# sch_USB3_0.net
KiCad netlist of a schematic drawn in Altium Designer
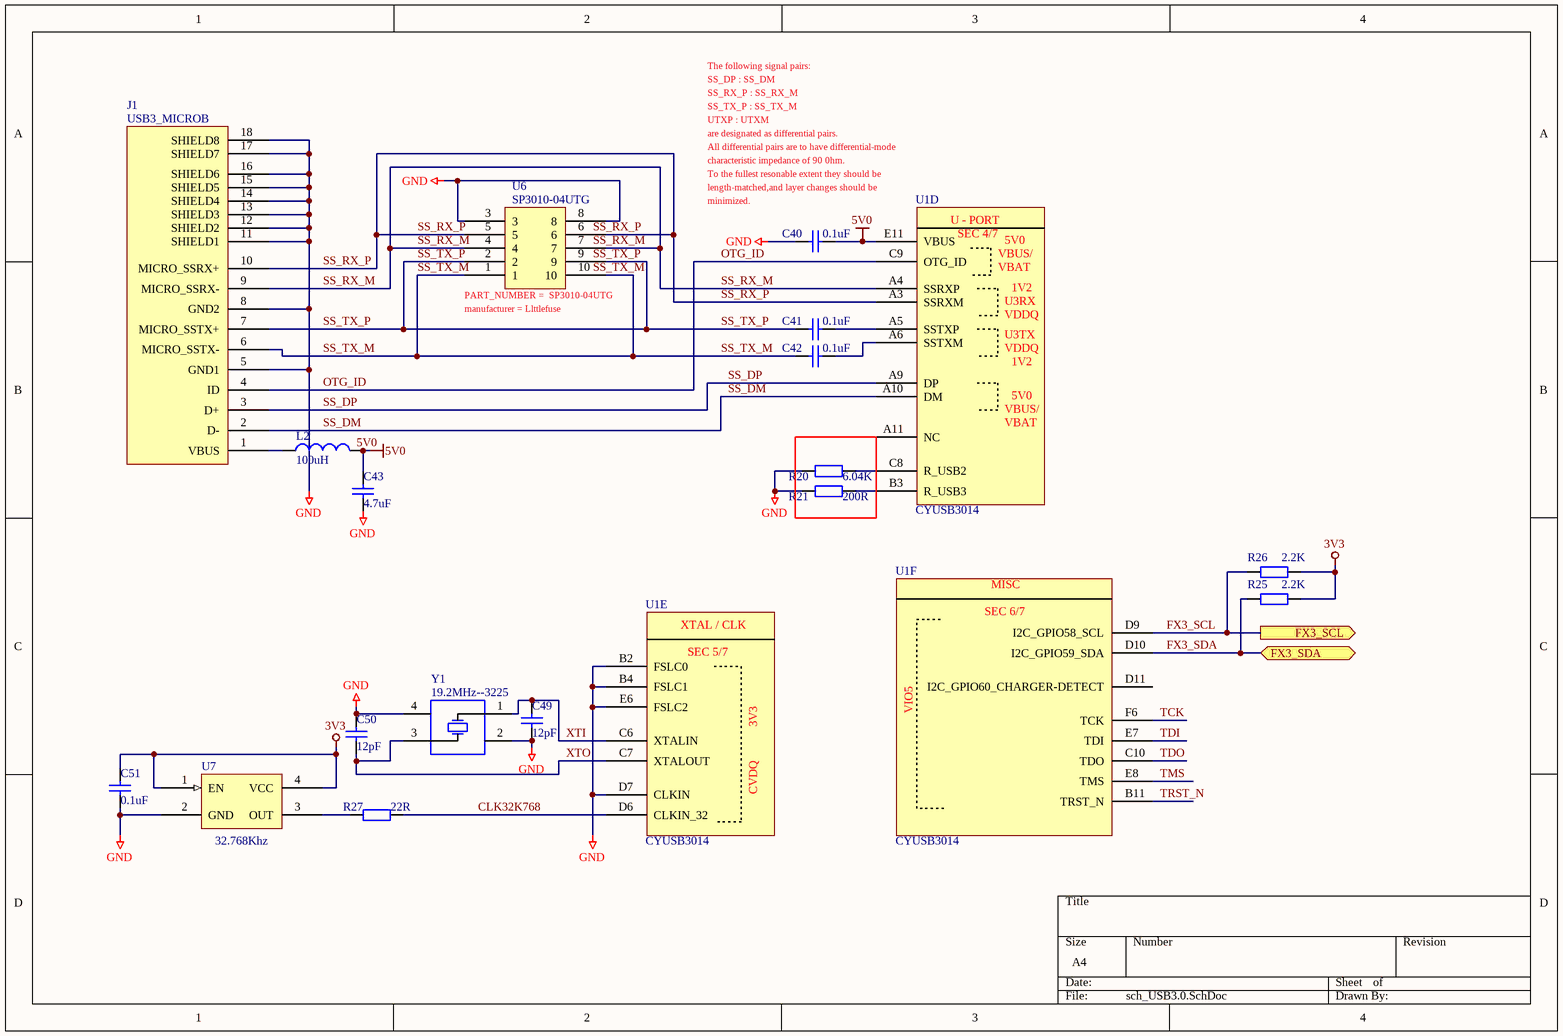
[diagram p0: sch_USB3.0.SchDoc]

(export (version "E")
  (design (tool "Eeschema 10.0.6"))
  (components
    (comp (ref "C40")
      (value "0.1uF")
      (footprint "0402C")
      (description "Capacitor")
      (fields (field (name "PUBLISHER") "Altium Limited"))
      (libsource (lib "Miscellaneous Devices") (part "Cap"))
    )
    (comp (ref "C41")
      (value "0.1uF")
      (footprint "0402C")
      (description "Capacitor")
      (fields (field (name "PUBLISHER") "Altium Limited"))
      (libsource (lib "Miscellaneous Devices") (part "Cap"))
    )
    (comp (ref "C42")
      (value "0.1uF")
      (footprint "0402C")
      (description "Capacitor")
      (fields (field (name "PUBLISHER") "Altium Limited"))
      (libsource (lib "Miscellaneous Devices") (part "Cap"))
    )
    (comp (ref "C43")
      (value "4.7uF")
      (description "Capacitor")
      (fields (field (name "PUBLISHER") "Altium Limited"))
      (libsource (lib "Miscellaneous Devices") (part "Cap"))
    )
    (comp (ref "C49")
      (value "12pF")
      (footprint "0402C")
      (description "Capacitor")
      (fields (field (name "PUBLISHER") "Altium Limited"))
      (libsource (lib "Miscellaneous Devices") (part "Cap"))
    )
    (comp (ref "C50")
      (value "12pF")
      (footprint "0402C")
      (description "Capacitor")
      (fields (field (name "PUBLISHER") "Altium Limited"))
      (libsource (lib "Miscellaneous Devices") (part "Cap"))
    )
    (comp (ref "C51")
      (value "0.1uF")
      (footprint "0402C")
      (description "Capacitor")
      (fields (field (name "PUBLISHER") "Altium Limited"))
      (libsource (lib "Miscellaneous Devices") (part "Cap"))
    )
    (comp (ref "J1")
      (value "USB3_MICROB")
      (footprint "USB3_BA_P65L130W51H28")
      (libsource (lib "SZG") (part "USB3_MICROB"))
    )
    (comp (ref "L2")
      (value "100uH")
      (description "Inductor")
      (libsource (lib "SWUST_ROBOT") (part "Inductor"))
    )
    (comp (ref "R20")
      (value "6.04K")
      (footprint "0402R")
      (description "Resistor")
      (fields (field (name "PUBLISHER") "Altium Limited"))
      (libsource (lib "SZG") (part "Resistor"))
    )
    (comp (ref "R21")
      (value "200R")
      (footprint "0402R")
      (description "Resistor")
      (fields (field (name "PUBLISHER") "Altium Limited"))
      (libsource (lib "SZG") (part "Resistor"))
    )
    (comp (ref "R25")
      (value "2.2K")
      (footprint "0402R")
      (description "Resistor")
      (fields (field (name "PUBLISHER") "Altium Limited"))
      (libsource (lib "SZG") (part "Resistor"))
    )
    (comp (ref "R26")
      (value "2.2K")
      (footprint "0402R")
      (description "Resistor")
      (fields (field (name "PUBLISHER") "Altium Limited"))
      (libsource (lib "SZG") (part "Resistor"))
    )
    (comp (ref "R27")
      (value "22R")
      (footprint "0402R")
      (description "Resistor")
      (fields (field (name "PUBLISHER") "Altium Limited"))
      (libsource (lib "SZG") (part "Resistor"))
    )
    (comp (ref "U1")
      (value "CYUSB3014")
      (footprint "FBGA121_P80L100W100H11")
      (libsource (lib "TXW") (part "CYUSB3014"))
    )
    (comp (ref "U6")
      (value "SP3010-04UTG")
      (footprint "UDFN10_SON_P50L25W10H55")
      (libsource (lib "SZG") (part "SP3010-04UTG"))
    )
    (comp (ref "U7")
      (value "XTAL-3225")
      (footprint "XTAL_3225")
      (libsource (lib "常用晶振器件图SCH") (part "XTAL."))
    )
    (comp (ref "Y1")
      (value "19.2MHz--3225")
      (footprint "XTAL_3225")
      (description "Crystal Oscillator")
      (libsource (lib "常用晶振器件图SCH") (part "XTAL"))
    )
  )
  (nets
    (net (code "1") (name "/CLK32K768") (class "Default")
      (node (ref "R27") (pin "1") (pinfunction "1_1") (pintype "passive"))
      (node (ref "U1") (pin "D6") (pinfunction "CLKIN_32_D6") (pintype "passive"))
    )
    (net (code "2") (name "/FX3_SCL") (class "Default")
      (node (ref "R26") (pin "2") (pinfunction "2_2") (pintype "passive"))
      (node (ref "U1") (pin "D9") (pinfunction "I2C_GPIO58_SCL_D9") (pintype "passive"))
    )
    (net (code "3") (name "/FX3_SDA") (class "Default")
      (node (ref "R25") (pin "2") (pinfunction "2_2") (pintype "passive"))
      (node (ref "U1") (pin "D10") (pinfunction "I2C_GPIO59_SDA_D10") (pintype "passive"))
    )
    (net (code "4") (name "/OTG_ID") (class "Default")
      (node (ref "J1") (pin "4") (pinfunction "ID_4") (pintype "power_in"))
      (node (ref "U1") (pin "C9") (pinfunction "OTG_ID_C9") (pintype "power_in"))
    )
    (net (code "5") (name "/SS_DM") (class "Default")
      (node (ref "J1") (pin "2") (pinfunction "D-_2") (pintype "power_in"))
      (node (ref "U1") (pin "A10") (pinfunction "DM_A10") (pintype "power_in"))
    )
    (net (code "6") (name "/SS_DP") (class "Default")
      (node (ref "J1") (pin "3") (pinfunction "D+_3") (pintype "power_in"))
      (node (ref "U1") (pin "A9") (pinfunction "DP_A9") (pintype "power_in"))
    )
    (net (code "7") (name "/SS_RX_M") (class "Default")
      (node (ref "J1") (pin "9") (pinfunction "MICRO_SSRX-_9") (pintype "power_in"))
      (node (ref "U1") (pin "A4") (pinfunction "SSRXP_A4") (pintype "power_in"))
      (node (ref "U6") (pin "4") (pinfunction "4_4") (pintype "passive"))
      (node (ref "U6") (pin "7") (pinfunction "7_7") (pintype "passive"))
    )
    (net (code "8") (name "/SS_RX_P") (class "Default")
      (node (ref "J1") (pin "10") (pinfunction "MICRO_SSRX+_10") (pintype "power_in"))
      (node (ref "U1") (pin "A3") (pinfunction "SSRXM_A3") (pintype "power_in"))
      (node (ref "U6") (pin "5") (pinfunction "5_5") (pintype "passive"))
      (node (ref "U6") (pin "6") (pinfunction "6_6") (pintype "passive"))
    )
    (net (code "9") (name "/SS_TX_M") (class "Default")
      (node (ref "C42") (pin "2") (pinfunction "2_2") (pintype "passive"))
      (node (ref "J1") (pin "6") (pinfunction "MICRO_SSTX-_6") (pintype "power_in"))
      (node (ref "U6") (pin "1") (pinfunction "1_1") (pintype "passive"))
      (node (ref "U6") (pin "10") (pinfunction "10_10") (pintype "passive"))
    )
    (net (code "10") (name "/SS_TX_P") (class "Default")
      (node (ref "C41") (pin "2") (pinfunction "2_2") (pintype "passive"))
      (node (ref "J1") (pin "7") (pinfunction "MICRO_SSTX+_7") (pintype "power_in"))
      (node (ref "U6") (pin "2") (pinfunction "2_2") (pintype "passive"))
      (node (ref "U6") (pin "9") (pinfunction "9_9") (pintype "passive"))
    )
    (net (code "11") (name "/TCK") (class "Default")
      (node (ref "U1") (pin "F6") (pinfunction "TCK_F6") (pintype "passive"))
    )
    (net (code "12") (name "/TDI") (class "Default")
      (node (ref "U1") (pin "E7") (pinfunction "TDI_E7") (pintype "passive"))
    )
    (net (code "13") (name "/TDO") (class "Default")
      (node (ref "U1") (pin "C10") (pinfunction "TDO_C10") (pintype "passive"))
    )
    (net (code "14") (name "/TMS") (class "Default")
      (node (ref "U1") (pin "E8") (pinfunction "TMS_E8") (pintype "passive"))
    )
    (net (code "15") (name "/TRST_N") (class "Default")
      (node (ref "U1") (pin "B11") (pinfunction "TRST_N_B11") (pintype "passive"))
    )
    (net (code "16") (name "/XTI") (class "Default")
      (node (ref "C49") (pin "2") (pinfunction "2_2") (pintype "passive"))
      (node (ref "U1") (pin "C6") (pinfunction "XTALIN_C6") (pintype "passive"))
      (node (ref "Y1") (pin "1") (pinfunction "1_1") (pintype "passive"))
    )
    (net (code "17") (name "/XTO") (class "Default")
      (node (ref "C50") (pin "1") (pinfunction "1_1") (pintype "passive"))
      (node (ref "U1") (pin "C7") (pinfunction "XTALOUT_C7") (pintype "passive"))
      (node (ref "Y1") (pin "3") (pinfunction "3_3") (pintype "passive"))
    )
    (net (code "18") (name "3V3") (class "Default")
      (node (ref "C51") (pin "2") (pinfunction "2_2") (pintype "passive"))
      (node (ref "R25") (pin "1") (pinfunction "1_1") (pintype "passive"))
      (node (ref "R26") (pin "1") (pinfunction "1_1") (pintype "passive"))
      (node (ref "U7") (pin "1") (pinfunction "EN_1") (pintype "input"))
      (node (ref "U7") (pin "4") (pinfunction "VCC_4") (pintype "passive"))
    )
    (net (code "19") (name "5V0") (class "Default")
      (node (ref "C40") (pin "1") (pinfunction "1_1") (pintype "passive"))
      (node (ref "C43") (pin "2") (pinfunction "2_2") (pintype "passive"))
      (node (ref "L2") (pin "2") (pinfunction "2_2") (pintype "passive"))
      (node (ref "U1") (pin "E11") (pinfunction "VBUS_E11") (pintype "power_in"))
    )
    (net (code "20") (name "GND") (class "Default")
      (node (ref "C40") (pin "2") (pinfunction "2_2") (pintype "passive"))
      (node (ref "C43") (pin "1") (pinfunction "1_1") (pintype "passive"))
      (node (ref "C49") (pin "1") (pinfunction "1_1") (pintype "passive"))
      (node (ref "C50") (pin "2") (pinfunction "2_2") (pintype "passive"))
      (node (ref "C51") (pin "1") (pinfunction "1_1") (pintype "passive"))
      (node (ref "J1") (pin "11") (pinfunction "SHIELD1_11") (pintype "power_in"))
      (node (ref "J1") (pin "12") (pinfunction "SHIELD2_12") (pintype "power_in"))
      (node (ref "J1") (pin "13") (pinfunction "SHIELD3_13") (pintype "power_in"))
      (node (ref "J1") (pin "14") (pinfunction "SHIELD4_14") (pintype "power_in"))
      (node (ref "J1") (pin "15") (pinfunction "SHIELD5_15") (pintype "power_in"))
      (node (ref "J1") (pin "16") (pinfunction "SHIELD6_16") (pintype "power_in"))
      (node (ref "J1") (pin "17") (pinfunction "SHIELD7_17") (pintype "power_in"))
      (node (ref "J1") (pin "18") (pinfunction "SHIELD8_18") (pintype "power_in"))
      (node (ref "J1") (pin "5") (pinfunction "GND1_5") (pintype "power_in"))
      (node (ref "J1") (pin "8") (pinfunction "GND2_8") (pintype "power_in"))
      (node (ref "R20") (pin "2") (pinfunction "2_2") (pintype "passive"))
      (node (ref "R21") (pin "2") (pinfunction "2_2") (pintype "passive"))
      (node (ref "U1") (pin "B2") (pinfunction "FSLC0_B2") (pintype "passive"))
      (node (ref "U1") (pin "B4") (pinfunction "FSLC1_B4") (pintype "passive"))
      (node (ref "U1") (pin "D7") (pinfunction "CLKIN_D7") (pintype "passive"))
      (node (ref "U1") (pin "E6") (pinfunction "FSLC2_E6") (pintype "passive"))
      (node (ref "U6") (pin "3") (pinfunction "3_3") (pintype "passive"))
      (node (ref "U6") (pin "8") (pinfunction "8_8") (pintype "passive"))
      (node (ref "U7") (pin "2") (pinfunction "GND_2") (pintype "passive"))
      (node (ref "Y1") (pin "2") (pinfunction "2_2") (pintype "passive"))
      (node (ref "Y1") (pin "4") (pinfunction "4_4") (pintype "passive"))
    )
    (net (code "21") (name "Net-(J1-VBUS)") (class "Default")
      (node (ref "J1") (pin "1") (pinfunction "VBUS_1") (pintype "power_in"))
      (node (ref "L2") (pin "1") (pinfunction "1_1") (pintype "passive"))
    )
    (net (code "22") (name "Net-(U1D-R_USB2)") (class "Default")
      (node (ref "R20") (pin "1") (pinfunction "1_1") (pintype "passive"))
      (node (ref "U1") (pin "C8") (pinfunction "R_USB2_C8") (pintype "power_in"))
    )
    (net (code "23") (name "Net-(U1D-R_USB3)") (class "Default")
      (node (ref "R21") (pin "1") (pinfunction "1_1") (pintype "passive"))
      (node (ref "U1") (pin "B3") (pinfunction "R_USB3_B3") (pintype "power_in"))
    )
    (net (code "24") (name "Net-(U1D-SSTXM)") (class "Default")
      (node (ref "C42") (pin "1") (pinfunction "1_1") (pintype "passive"))
      (node (ref "U1") (pin "A6") (pinfunction "SSTXM_A6") (pintype "power_in"))
    )
    (net (code "25") (name "Net-(U1D-SSTXP)") (class "Default")
      (node (ref "C41") (pin "1") (pinfunction "1_1") (pintype "passive"))
      (node (ref "U1") (pin "A5") (pinfunction "SSTXP_A5") (pintype "power_in"))
    )
    (net (code "26") (name "Net-(U7-OUT)") (class "Default")
      (node (ref "R27") (pin "2") (pinfunction "2_2") (pintype "passive"))
      (node (ref "U7") (pin "3") (pinfunction "OUT_3") (pintype "passive"))
    )
    (net (code "27") (name "unconnected-(U1D-NC-PadA11)") (class "Default")
      (node (ref "U1") (pin "A11") (pinfunction "NC_A11") (pintype "power_in"))
    )
    (net (code "28") (name "unconnected-(U1F-I2C_GPIO60_CHARGER-DETECT-PadD11)") (class "Default")
      (node (ref "U1") (pin "D11") (pinfunction "I2C_GPIO60_CHARGER-DETECT_D11") (pintype "passive"))
    )
  )
)
